# WCE_Camera_MCU.net
KiCad netlist of a schematic drawn in Altium Designer
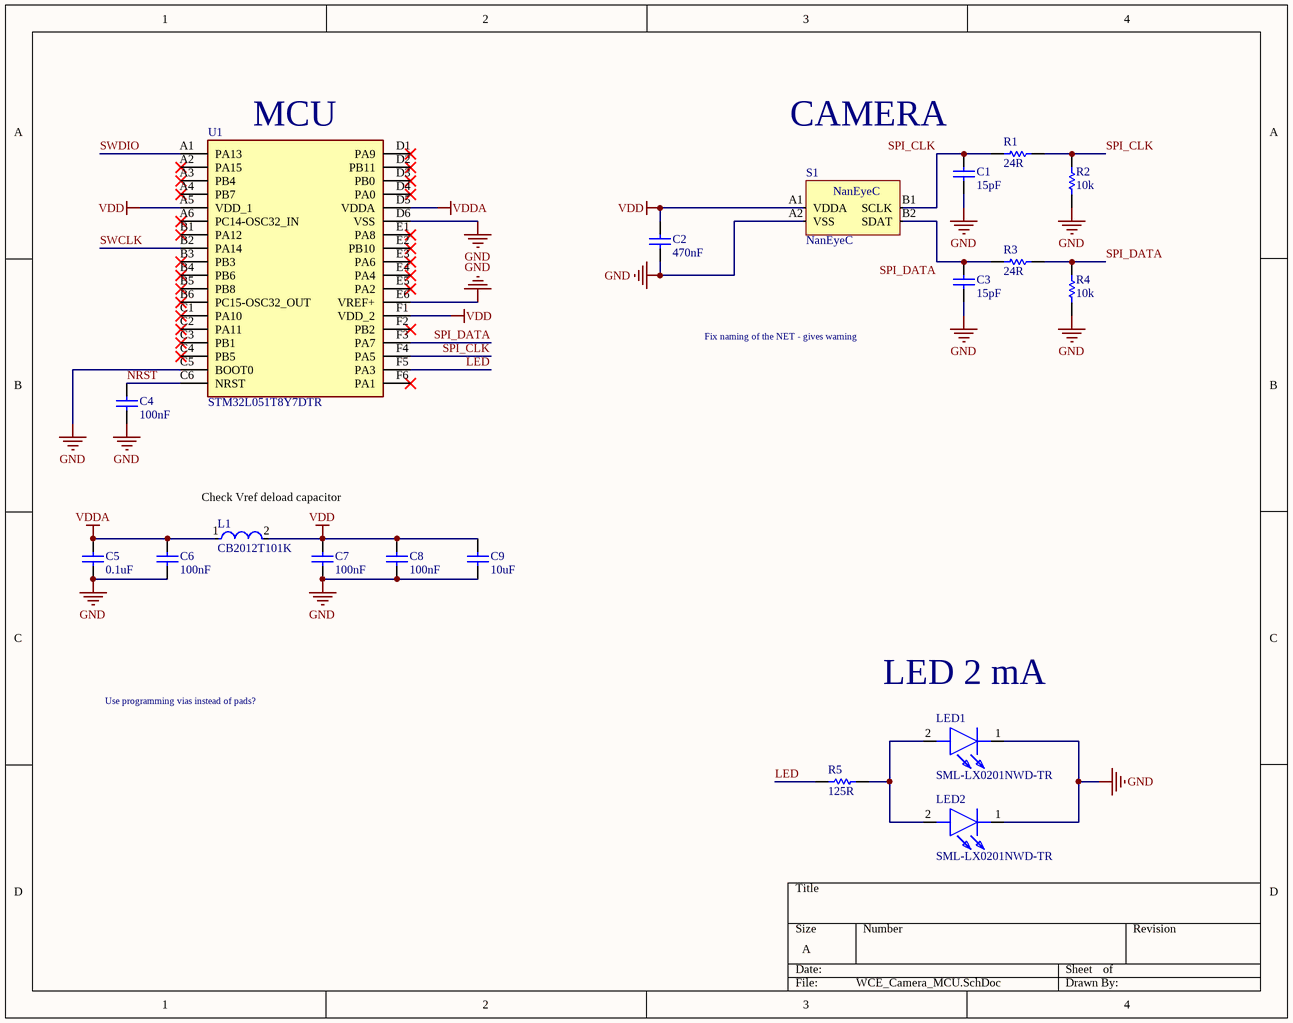
[diagram p0: WCE_Camera_MCU.SchDoc]

(export (version "E")
  (design (tool "Eeschema 10.0.6"))
  (components
    (comp (ref "C1")
      (value "15pF")
      (footprint "CAPC0603X33X15LL03T05")
      (description "Capacitor 15 pF 0201 XR5")
      (fields
        (field (name "PART NUMBER") "02016D104KAT2A")
        (field (name "MANUFACTURER") "AVX Interconnect / Elco")
      )
      (libsource (lib "Altium Content Vault") (part "CAP"))
    )
    (comp (ref "C2")
      (value "470nF")
      (footprint "CAPC0603X33X15LL03T05")
      (description "Capacitor 470 nF 0201 XR5")
      (fields
        (field (name "PART NUMBER") "02016D104KAT2A")
        (field (name "MANUFACTURER") "AVX Interconnect / Elco")
      )
      (libsource (lib "Altium Content Vault") (part "CAP"))
    )
    (comp (ref "C3")
      (value "15pF")
      (footprint "CAPC0603X33X15LL03T05")
      (description "Capacitor 15 pF 0201 XR5")
      (fields
        (field (name "PART NUMBER") "02016D104KAT2A")
        (field (name "MANUFACTURER") "AVX Interconnect / Elco")
      )
      (libsource (lib "Altium Content Vault") (part "CAP"))
    )
    (comp (ref "C4")
      (value "100nF")
      (footprint "CAPC0603X33X15LL03T05")
      (description "Capacitor 100 nF 0201 XR5")
      (fields
        (field (name "PART NUMBER") "02016D104KAT2A")
        (field (name "MANUFACTURER") "AVX Interconnect / Elco")
      )
      (libsource (lib "Altium Content Vault") (part "CAP"))
    )
    (comp (ref "C5")
      (value "0.1uF")
      (footprint "CAPC0603X33X15LL03T05")
      (description "Capacitor 0.1 uF 0201 XR5")
      (fields
        (field (name "PART NUMBER") "02016D104KAT2A")
        (field (name "MANUFACTURER") "AVX Interconnect / Elco")
      )
      (libsource (lib "Altium Content Vault") (part "CAP"))
    )
    (comp (ref "C6")
      (value "100nF")
      (footprint "CAPC0603X33X15LL03T05")
      (description "Capacitor 100 nF 0201 XR5")
      (fields
        (field (name "PART NUMBER") "02016D104KAT2A")
        (field (name "MANUFACTURER") "AVX Interconnect / Elco")
      )
      (libsource (lib "Altium Content Vault") (part "CAP"))
    )
    (comp (ref "C7")
      (value "100nF")
      (footprint "CAPC0603X33X15LL03T05")
      (description "Capacitor 100 nF 0201 XR5")
      (fields
        (field (name "PART NUMBER") "02016D104KAT2A")
        (field (name "MANUFACTURER") "AVX Interconnect / Elco")
      )
      (libsource (lib "Altium Content Vault") (part "CAP"))
    )
    (comp (ref "C8")
      (value "100nF")
      (footprint "CAPC0603X33X15LL03T05")
      (description "Capacitor 100 nF 0201 XR5")
      (fields
        (field (name "PART NUMBER") "02016D104KAT2A")
        (field (name "MANUFACTURER") "AVX Interconnect / Elco")
      )
      (libsource (lib "Altium Content Vault") (part "CAP"))
    )
    (comp (ref "C9")
      (value "10uF")
      (footprint "CAPC0603X33X15LL03T05")
      (description "Capacitor 10 uF 0201 XR5")
      (fields
        (field (name "PART NUMBER") "02016D104KAT2A")
        (field (name "MANUFACTURER") "AVX Interconnect / Elco")
      )
      (libsource (lib "Altium Content Vault") (part "CAP"))
    )
    (comp (ref "L1")
      (value "CB2012T101K")
      (footprint "FP-CB2012-MFG")
      (description "SMD Inductors 100uH ±10% 0.13A 9.1Ω 0805")
      (fields (field (name "TOLERANCE") "10%"))
      (libsource (lib "Altium Content Vault") (part "725321dda6339637d4d059423bc1c3c"))
    )
    (comp (ref "LED1")
      (value "SML-LX0201NWD-TR")
      (footprint "SML-LX0201NWD-TR")
      (description "Lumex LED 0201 SML-LX0201NWD-TR")
      (libsource (lib "WCE_thesis") (part "SML-LX0201NWD-TR"))
    )
    (comp (ref "LED2")
      (value "SML-LX0201NWD-TR")
      (footprint "SML-LX0201NWD-TR")
      (description "Lumex LED 0201 SML-LX0201NWD-TR")
      (libsource (lib "WCE_thesis") (part "SML-LX0201NWD-TR"))
    )
    (comp (ref "R1")
      (value "24R")
      (footprint "RESC0603X28X15NL5T05")
      (description "Thin film Resistor 125 OHM 0.1%-1% 100 mW (1/10 W) 0201")
      (fields (field (name "TOLERANCE") "5%"))
      (libsource (lib "Altium Content Vault") (part "RES-2"))
    )
    (comp (ref "R2")
      (value "10k")
      (footprint "RESC0603X28X15NL5T05")
      (description "Thin film Resistor 125 OHM 0.1%-1% 100 mW (1/10 W) 0201")
      (fields (field (name "TOLERANCE") "5%"))
      (libsource (lib "Altium Content Vault") (part "RES-2"))
    )
    (comp (ref "R3")
      (value "24R")
      (footprint "RESC0603X28X15NL5T05")
      (description "Thin film Resistor 125 OHM 0.1%-1% 100 mW (1/10 W) 0201")
      (fields (field (name "TOLERANCE") "5%"))
      (libsource (lib "Altium Content Vault") (part "RES-2"))
    )
    (comp (ref "R4")
      (value "10k")
      (footprint "RESC0603X28X15NL5T05")
      (description "Thin film Resistor 125 OHM 0.1%-1% 100 mW (1/10 W) 0201")
      (fields (field (name "TOLERANCE") "5%"))
      (libsource (lib "Altium Content Vault") (part "RES-2"))
    )
    (comp (ref "R5")
      (value "125R")
      (footprint "RESC0603X28X15NL5T05")
      (description "Thin film Resistor 125 OHM 0.1%-1% 100 mW (1/10 W) 0201")
      (fields (field (name "TOLERANCE") "5%"))
      (libsource (lib "Altium Content Vault") (part "RES-2"))
    )
    (comp (ref "S1")
      (value "NanEyeC")
      (footprint "NanEyeC")
      (description "Camera module NanEyeC from AMS. The Part will be delivered by us")
      (libsource (lib "WCE_thesis") (part "NanEyeC"))
    )
    (comp (ref "U1")
      (value "STM32L051T8Y7DTR")
      (footprint "STM32L051T8Y7DTR")
      (description "STM microcontroller STM32L051T8Y7DTR WLCSP36")
      (libsource (lib "WCE_thesis") (part "STM32L051T8Y7DTR"))
    )
  )
  (nets
    (net (code "1") (name "/LED") (class "Default")
      (node (ref "R5") (pin "1") (pinfunction "1_1") (pintype "passive"))
      (node (ref "U1") (pin "F5") (pinfunction "PA3_F5") (pintype "passive"))
    )
    (net (code "2") (name "/NRST") (class "Default")
      (node (ref "C4") (pin "2") (pinfunction "2_2") (pintype "passive"))
      (node (ref "U1") (pin "C6") (pinfunction "NRST_C6") (pintype "passive"))
    )
    (net (code "3") (name "/SPI_CLK") (class "Default")
      (node (ref "C1") (pin "2") (pinfunction "2_2") (pintype "passive"))
      (node (ref "R1") (pin "1") (pinfunction "1_1") (pintype "passive"))
      (node (ref "R1") (pin "2") (pinfunction "2_2") (pintype "passive"))
      (node (ref "R2") (pin "2") (pinfunction "2_2") (pintype "passive"))
      (node (ref "S1") (pin "B1") (pinfunction "SCLK_B1") (pintype "power_in"))
      (node (ref "U1") (pin "F4") (pinfunction "PA5_F4") (pintype "passive"))
    )
    (net (code "4") (name "/SPI_DATA") (class "Default")
      (node (ref "C3") (pin "2") (pinfunction "2_2") (pintype "passive"))
      (node (ref "R3") (pin "1") (pinfunction "1_1") (pintype "passive"))
      (node (ref "R3") (pin "2") (pinfunction "2_2") (pintype "passive"))
      (node (ref "R4") (pin "2") (pinfunction "2_2") (pintype "passive"))
      (node (ref "S1") (pin "B2") (pinfunction "SDAT_B2") (pintype "passive"))
      (node (ref "U1") (pin "F3") (pinfunction "PA7_F3") (pintype "passive"))
    )
    (net (code "5") (name "/SWCLK") (class "Default")
      (node (ref "U1") (pin "B2") (pinfunction "PA14_B2") (pintype "passive"))
    )
    (net (code "6") (name "/SWDIO") (class "Default")
      (node (ref "U1") (pin "A1") (pinfunction "PA13_A1") (pintype "passive"))
    )
    (net (code "7") (name "GND") (class "Default")
      (node (ref "C1") (pin "1") (pinfunction "1_1") (pintype "passive"))
      (node (ref "C2") (pin "1") (pinfunction "1_1") (pintype "passive"))
      (node (ref "C3") (pin "1") (pinfunction "1_1") (pintype "passive"))
      (node (ref "C4") (pin "1") (pinfunction "1_1") (pintype "passive"))
      (node (ref "C5") (pin "1") (pinfunction "1_1") (pintype "passive"))
      (node (ref "C6") (pin "1") (pinfunction "1_1") (pintype "passive"))
      (node (ref "C7") (pin "1") (pinfunction "1_1") (pintype "passive"))
      (node (ref "C8") (pin "1") (pinfunction "1_1") (pintype "passive"))
      (node (ref "C9") (pin "1") (pinfunction "1_1") (pintype "passive"))
      (node (ref "LED1") (pin "1") (pinfunction "K_1") (pintype "passive"))
      (node (ref "LED2") (pin "1") (pinfunction "K_1") (pintype "passive"))
      (node (ref "R2") (pin "1") (pinfunction "1_1") (pintype "passive"))
      (node (ref "R4") (pin "1") (pinfunction "1_1") (pintype "passive"))
      (node (ref "S1") (pin "A2") (pinfunction "VSS_A2") (pintype "passive"))
      (node (ref "U1") (pin "C5") (pinfunction "BOOT0_C5") (pintype "passive"))
      (node (ref "U1") (pin "D6") (pinfunction "VSS_D6") (pintype "passive"))
      (node (ref "U1") (pin "E6") (pinfunction "VREF+_E6") (pintype "passive"))
    )
    (net (code "8") (name "Net-(LED1-A)") (class "Default")
      (node (ref "LED1") (pin "2") (pinfunction "A_2") (pintype "passive"))
      (node (ref "LED2") (pin "2") (pinfunction "A_2") (pintype "passive"))
      (node (ref "R5") (pin "2") (pinfunction "2_2") (pintype "passive"))
    )
    (net (code "9") (name "VDD") (class "Default")
      (node (ref "C2") (pin "2") (pinfunction "2_2") (pintype "passive"))
      (node (ref "C7") (pin "2") (pinfunction "2_2") (pintype "passive"))
      (node (ref "C8") (pin "2") (pinfunction "2_2") (pintype "passive"))
      (node (ref "C9") (pin "2") (pinfunction "2_2") (pintype "passive"))
      (node (ref "L1") (pin "2") (pinfunction "2_2") (pintype "passive"))
      (node (ref "S1") (pin "A1") (pinfunction "VDDA_A1") (pintype "power_in"))
      (node (ref "U1") (pin "A5") (pinfunction "VDD_1_A5") (pintype "passive"))
      (node (ref "U1") (pin "F1") (pinfunction "VDD_2_F1") (pintype "passive"))
    )
    (net (code "10") (name "VDDA") (class "Default")
      (node (ref "C5") (pin "2") (pinfunction "2_2") (pintype "passive"))
      (node (ref "C6") (pin "2") (pinfunction "2_2") (pintype "passive"))
      (node (ref "L1") (pin "1") (pinfunction "1_1") (pintype "passive"))
      (node (ref "U1") (pin "D5") (pinfunction "VDDA_D5") (pintype "passive"))
    )
    (net (code "11") (name "unconnected-(U1-PA0-PadD4)") (class "Default")
      (node (ref "U1") (pin "D4") (pinfunction "PA0_D4") (pintype "passive+no_connect"))
    )
    (net (code "12") (name "unconnected-(U1-PA1-PadF6)") (class "Default")
      (node (ref "U1") (pin "F6") (pinfunction "PA1_F6") (pintype "passive+no_connect"))
    )
    (net (code "13") (name "unconnected-(U1-PA2-PadE5)") (class "Default")
      (node (ref "U1") (pin "E5") (pinfunction "PA2_E5") (pintype "passive+no_connect"))
    )
    (net (code "14") (name "unconnected-(U1-PA4-PadE4)") (class "Default")
      (node (ref "U1") (pin "E4") (pinfunction "PA4_E4") (pintype "passive+no_connect"))
    )
    (net (code "15") (name "unconnected-(U1-PA6-PadE3)") (class "Default")
      (node (ref "U1") (pin "E3") (pinfunction "PA6_E3") (pintype "passive+no_connect"))
    )
    (net (code "16") (name "unconnected-(U1-PA8-PadE1)") (class "Default")
      (node (ref "U1") (pin "E1") (pinfunction "PA8_E1") (pintype "passive+no_connect"))
    )
    (net (code "17") (name "unconnected-(U1-PA9-PadD1)") (class "Default")
      (node (ref "U1") (pin "D1") (pinfunction "PA9_D1") (pintype "passive+no_connect"))
    )
    (net (code "18") (name "unconnected-(U1-PA10-PadC1)") (class "Default")
      (node (ref "U1") (pin "C1") (pinfunction "PA10_C1") (pintype "passive+no_connect"))
    )
    (net (code "19") (name "unconnected-(U1-PA11-PadC2)") (class "Default")
      (node (ref "U1") (pin "C2") (pinfunction "PA11_C2") (pintype "passive+no_connect"))
    )
    (net (code "20") (name "unconnected-(U1-PA12-PadB1)") (class "Default")
      (node (ref "U1") (pin "B1") (pinfunction "PA12_B1") (pintype "passive+no_connect"))
    )
    (net (code "21") (name "unconnected-(U1-PA15-PadA2)") (class "Default")
      (node (ref "U1") (pin "A2") (pinfunction "PA15_A2") (pintype "passive+no_connect"))
    )
    (net (code "22") (name "unconnected-(U1-PB0-PadD3)") (class "Default")
      (node (ref "U1") (pin "D3") (pinfunction "PB0_D3") (pintype "passive+no_connect"))
    )
    (net (code "23") (name "unconnected-(U1-PB1-PadC3)") (class "Default")
      (node (ref "U1") (pin "C3") (pinfunction "PB1_C3") (pintype "passive+no_connect"))
    )
    (net (code "24") (name "unconnected-(U1-PB2-PadF2)") (class "Default")
      (node (ref "U1") (pin "F2") (pinfunction "PB2_F2") (pintype "passive+no_connect"))
    )
    (net (code "25") (name "unconnected-(U1-PB3-PadB3)") (class "Default")
      (node (ref "U1") (pin "B3") (pinfunction "PB3_B3") (pintype "passive+no_connect"))
    )
    (net (code "26") (name "unconnected-(U1-PB4-PadA3)") (class "Default")
      (node (ref "U1") (pin "A3") (pinfunction "PB4_A3") (pintype "passive+no_connect"))
    )
    (net (code "27") (name "unconnected-(U1-PB5-PadC4)") (class "Default")
      (node (ref "U1") (pin "C4") (pinfunction "PB5_C4") (pintype "passive+no_connect"))
    )
    (net (code "28") (name "unconnected-(U1-PB6-PadB4)") (class "Default")
      (node (ref "U1") (pin "B4") (pinfunction "PB6_B4") (pintype "passive+no_connect"))
    )
    (net (code "29") (name "unconnected-(U1-PB7-PadA4)") (class "Default")
      (node (ref "U1") (pin "A4") (pinfunction "PB7_A4") (pintype "passive+no_connect"))
    )
    (net (code "30") (name "unconnected-(U1-PB8-PadB5)") (class "Default")
      (node (ref "U1") (pin "B5") (pinfunction "PB8_B5") (pintype "passive+no_connect"))
    )
    (net (code "31") (name "unconnected-(U1-PB10-PadE2)") (class "Default")
      (node (ref "U1") (pin "E2") (pinfunction "PB10_E2") (pintype "passive+no_connect"))
    )
    (net (code "32") (name "unconnected-(U1-PB11-PadD2)") (class "Default")
      (node (ref "U1") (pin "D2") (pinfunction "PB11_D2") (pintype "passive+no_connect"))
    )
    (net (code "33") (name "unconnected-(U1-PC14-OSC32_IN-PadA6)") (class "Default")
      (node (ref "U1") (pin "A6") (pinfunction "PC14-OSC32_IN_A6") (pintype "passive+no_connect"))
    )
    (net (code "34") (name "unconnected-(U1-PC15-OSC32_OUT-PadB6)") (class "Default")
      (node (ref "U1") (pin "B6") (pinfunction "PC15-OSC32_OUT_B6") (pintype "passive+no_connect"))
    )
  )
)
